# mic_adapter.net
KiCad netlist of a schematic drawn in EAGLE
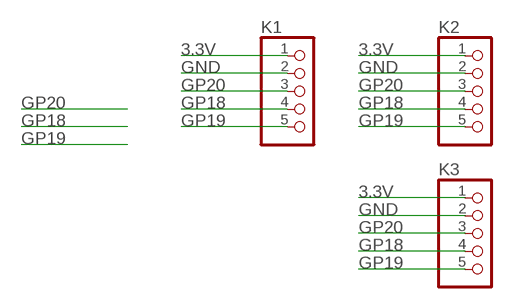
[diagram p0: schematic, sheet 1]

(export (version "E")
  (design (tool "Eeschema 10.0.6"))
  (components
    (comp (ref "K1")
      (value "HEADER-1X5SMT")
      (footprint "eagle-import:1X05_SMT")
      (libsource (lib "eagle-import") (part "HEADER-1X5SMT"))
    )
    (comp (ref "K2")
      (value "HEADER-1X5SMT")
      (footprint "eagle-import:1X05_SMT")
      (libsource (lib "eagle-import") (part "HEADER-1X5SMT"))
    )
    (comp (ref "K3")
      (value "HEADER-1X5SMT")
      (footprint "eagle-import:1X05_SMT")
      (libsource (lib "eagle-import") (part "HEADER-1X5SMT"))
    )
  )
  (nets
    (net (code "1") (name "/3.3V") (class "Default")
      (node (ref "K1") (pin "1") (pinfunction "1_1") (pintype "passive"))
      (node (ref "K2") (pin "1") (pinfunction "1_1") (pintype "passive"))
      (node (ref "K3") (pin "1") (pinfunction "1_1") (pintype "passive"))
    )
    (net (code "2") (name "/GND") (class "Default")
      (node (ref "K1") (pin "2") (pinfunction "2_2") (pintype "passive"))
      (node (ref "K2") (pin "2") (pinfunction "2_2") (pintype "passive"))
      (node (ref "K3") (pin "2") (pinfunction "2_2") (pintype "passive"))
    )
    (net (code "3") (name "/GP18") (class "Default")
      (node (ref "K1") (pin "4") (pinfunction "4_4") (pintype "passive"))
      (node (ref "K2") (pin "4") (pinfunction "4_4") (pintype "passive"))
      (node (ref "K3") (pin "4") (pinfunction "4_4") (pintype "passive"))
    )
    (net (code "4") (name "/GP19") (class "Default")
      (node (ref "K1") (pin "5") (pinfunction "5_5") (pintype "passive"))
      (node (ref "K2") (pin "5") (pinfunction "5_5") (pintype "passive"))
      (node (ref "K3") (pin "5") (pinfunction "5_5") (pintype "passive"))
    )
    (net (code "5") (name "/GP20") (class "Default")
      (node (ref "K1") (pin "3") (pinfunction "3_3") (pintype "passive"))
      (node (ref "K2") (pin "3") (pinfunction "3_3") (pintype "passive"))
      (node (ref "K3") (pin "3") (pinfunction "3_3") (pintype "passive"))
    )
  )
)
